# v1.net
KiCad netlist of a schematic drawn in EAGLE
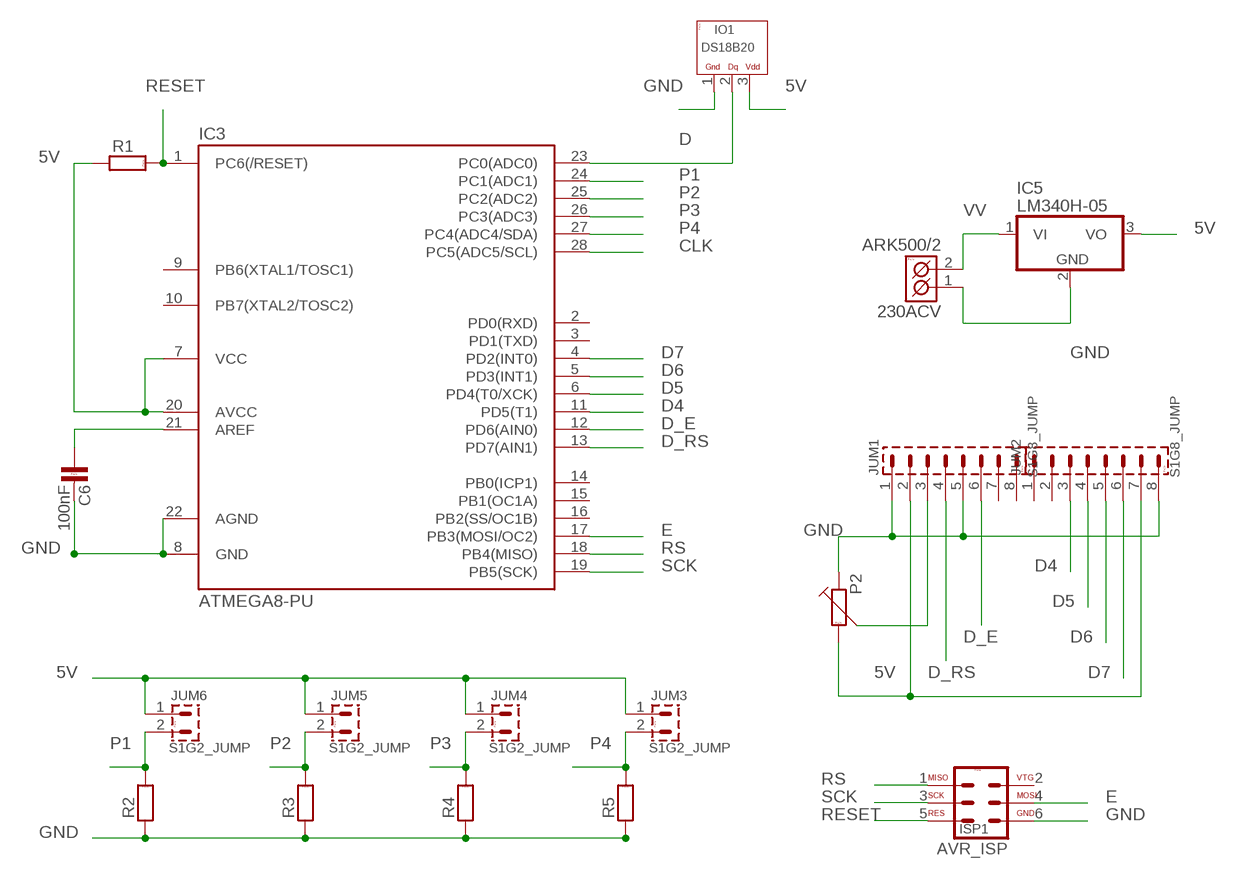
[diagram p0: schematic, sheet 1]

(export (version "E")
  (design (tool "Eeschema 10.0.6"))
  (components
    (comp (ref "230ACV")
      (value "ARK500/2")
      (footprint "eagle-import:ARK500_2")
      (libsource (lib "eagle-import") (part "ARK500/2"))
    )
    (comp (ref "C6")
      (value "100nF")
      (footprint "eagle-import:C-2,5")
      (libsource (lib "eagle-import") (part "C-KER_2,5"))
    )
    (comp (ref "IC3")
      (value "ATMEGA8-PU")
      (footprint "eagle-import:DIL28-3")
      (libsource (lib "eagle-import") (part "ATMEGA8-PU"))
    )
    (comp (ref "IC5")
      (value "LM340H-05")
      (footprint "eagle-import:TO220H")
      (libsource (lib "eagle-import") (part "LM340?-H05"))
    )
    (comp (ref "IO1")
      (value "DS18B20")
      (footprint "eagle-import:TO-92")
      (libsource (lib "eagle-import") (part "DS18B20"))
    )
    (comp (ref "ISP1")
      (value "AVR_ISP")
      (footprint "eagle-import:MLW06G")
      (libsource (lib "eagle-import") (part "AVR_ISP"))
    )
    (comp (ref "JUM1")
      (value "S1G8_JUMP")
      (footprint "eagle-import:S1G8_JUM")
      (libsource (lib "eagle-import") (part "S1G8_JUMP"))
    )
    (comp (ref "JUM2")
      (value "S1G8_JUMP")
      (footprint "eagle-import:S1G8_JUM")
      (libsource (lib "eagle-import") (part "S1G8_JUMP"))
    )
    (comp (ref "JUM3")
      (value "S1G2_JUMP")
      (footprint "eagle-import:S1G2_JUM")
      (libsource (lib "eagle-import") (part "S1G2_JUMP"))
    )
    (comp (ref "JUM4")
      (value "S1G2_JUMP")
      (footprint "eagle-import:S1G2_JUM")
      (libsource (lib "eagle-import") (part "S1G2_JUMP"))
    )
    (comp (ref "JUM5")
      (value "S1G2_JUMP")
      (footprint "eagle-import:S1G2_JUM")
      (libsource (lib "eagle-import") (part "S1G2_JUMP"))
    )
    (comp (ref "JUM6")
      (value "S1G2_JUMP")
      (footprint "eagle-import:S1G2_JUM")
      (libsource (lib "eagle-import") (part "S1G2_JUMP"))
    )
    (comp (ref "P2")
      (value "TRIMRPT6V")
      (footprint "eagle-import:PT6V")
      (libsource (lib "eagle-import") (part "TRIMRPT6V"))
    )
    (comp (ref "R1")
      (value "R_7,5")
      (footprint "eagle-import:R-7,5")
      (libsource (lib "eagle-import") (part "R_7,5"))
    )
    (comp (ref "R2")
      (value "R_7,5")
      (footprint "eagle-import:R-7,5")
      (libsource (lib "eagle-import") (part "R_7,5"))
    )
    (comp (ref "R3")
      (value "R_7,5")
      (footprint "eagle-import:R-7,5")
      (libsource (lib "eagle-import") (part "R_7,5"))
    )
    (comp (ref "R4")
      (value "R_7,5")
      (footprint "eagle-import:R-7,5")
      (libsource (lib "eagle-import") (part "R_7,5"))
    )
    (comp (ref "R5")
      (value "R_7,5")
      (footprint "eagle-import:R-7,5")
      (libsource (lib "eagle-import") (part "R_7,5"))
    )
  )
  (nets
    (net (code "1") (name "/5V") (class "Default")
      (node (ref "IC3") (pin "20") (pinfunction "AVCC_20") (pintype "passive"))
      (node (ref "IC3") (pin "7") (pinfunction "VCC_7") (pintype "power_in"))
      (node (ref "IC5") (pin "3") (pinfunction "VO_3") (pintype "passive"))
      (node (ref "IO1") (pin "3") (pinfunction "+VCC_3") (pintype "power_in"))
      (node (ref "JUM1") (pin "2") (pinfunction "2_2") (pintype "passive"))
      (node (ref "JUM2") (pin "7") (pinfunction "7_7") (pintype "passive"))
      (node (ref "JUM3") (pin "1") (pinfunction "1_1") (pintype "passive"))
      (node (ref "JUM4") (pin "1") (pinfunction "1_1") (pintype "passive"))
      (node (ref "JUM5") (pin "1") (pinfunction "1_1") (pintype "passive"))
      (node (ref "JUM6") (pin "1") (pinfunction "1_1") (pintype "passive"))
      (node (ref "P2") (pin "2") (pinfunction "2_2") (pintype "passive"))
      (node (ref "R1") (pin "1") (pinfunction "1_1") (pintype "passive"))
    )
    (net (code "2") (name "/CLK") (class "Default")
      (node (ref "IC3") (pin "28") (pinfunction "PC5(ADC5/SCL)_28") (pintype "bidirectional"))
    )
    (net (code "3") (name "/D") (class "Default")
      (node (ref "IC3") (pin "23") (pinfunction "PC0(ADC0)_23") (pintype "bidirectional"))
      (node (ref "IO1") (pin "2") (pinfunction "1WIRE_2") (pintype "bidirectional"))
    )
    (net (code "4") (name "/D4") (class "Default")
      (node (ref "IC3") (pin "11") (pinfunction "PD5(T1)_11") (pintype "bidirectional"))
      (node (ref "JUM2") (pin "3") (pinfunction "3_3") (pintype "passive"))
    )
    (net (code "5") (name "/D5") (class "Default")
      (node (ref "IC3") (pin "6") (pinfunction "PD4(T0/XCK)_6") (pintype "bidirectional"))
      (node (ref "JUM2") (pin "4") (pinfunction "4_4") (pintype "passive"))
    )
    (net (code "6") (name "/D6") (class "Default")
      (node (ref "IC3") (pin "5") (pinfunction "PD3(INT1)_5") (pintype "bidirectional"))
      (node (ref "JUM2") (pin "5") (pinfunction "5_5") (pintype "passive"))
    )
    (net (code "7") (name "/D7") (class "Default")
      (node (ref "IC3") (pin "4") (pinfunction "PD2(INT0)_4") (pintype "bidirectional"))
      (node (ref "JUM2") (pin "6") (pinfunction "6_6") (pintype "passive"))
    )
    (net (code "8") (name "/D_E") (class "Default")
      (node (ref "IC3") (pin "12") (pinfunction "PD6(AIN0)_12") (pintype "bidirectional"))
      (node (ref "JUM1") (pin "6") (pinfunction "6_6") (pintype "passive"))
    )
    (net (code "9") (name "/D_RS") (class "Default")
      (node (ref "IC3") (pin "13") (pinfunction "PD7(AIN1)_13") (pintype "bidirectional"))
      (node (ref "JUM1") (pin "4") (pinfunction "4_4") (pintype "passive"))
    )
    (net (code "10") (name "/E") (class "Default")
      (node (ref "IC3") (pin "17") (pinfunction "PB3(MOSI/OC2)_17") (pintype "bidirectional"))
      (node (ref "ISP1") (pin "4") (pinfunction "4_4") (pintype "passive"))
    )
    (net (code "11") (name "/GND") (class "Default")
      (node (ref "230ACV") (pin "1") (pinfunction "K1_1") (pintype "passive"))
      (node (ref "C6") (pin "2") (pinfunction "2_2") (pintype "passive"))
      (node (ref "IC3") (pin "22") (pinfunction "AGND_22") (pintype "power_in"))
      (node (ref "IC3") (pin "8") (pinfunction "GND_8") (pintype "power_in"))
      (node (ref "IC5") (pin "2") (pinfunction "GND_2") (pintype "passive"))
      (node (ref "IO1") (pin "1") (pinfunction "GND_1") (pintype "power_in"))
      (node (ref "ISP1") (pin "6") (pinfunction "6_6") (pintype "passive"))
      (node (ref "JUM1") (pin "1") (pinfunction "1_1") (pintype "passive"))
      (node (ref "JUM1") (pin "5") (pinfunction "5_5") (pintype "passive"))
      (node (ref "JUM2") (pin "8") (pinfunction "8_8") (pintype "passive"))
      (node (ref "P2") (pin "1") (pinfunction "1_1") (pintype "passive"))
      (node (ref "R2") (pin "1") (pinfunction "1_1") (pintype "passive"))
      (node (ref "R3") (pin "1") (pinfunction "1_1") (pintype "passive"))
      (node (ref "R4") (pin "1") (pinfunction "1_1") (pintype "passive"))
      (node (ref "R5") (pin "1") (pinfunction "1_1") (pintype "passive"))
    )
    (net (code "12") (name "/P1") (class "Default")
      (node (ref "IC3") (pin "24") (pinfunction "PC1(ADC1)_24") (pintype "bidirectional"))
      (node (ref "JUM6") (pin "2") (pinfunction "2_2") (pintype "passive"))
      (node (ref "R2") (pin "2") (pinfunction "2_2") (pintype "passive"))
    )
    (net (code "13") (name "/P2") (class "Default")
      (node (ref "IC3") (pin "25") (pinfunction "PC2(ADC2)_25") (pintype "bidirectional"))
      (node (ref "JUM5") (pin "2") (pinfunction "2_2") (pintype "passive"))
      (node (ref "R3") (pin "2") (pinfunction "2_2") (pintype "passive"))
    )
    (net (code "14") (name "/P3") (class "Default")
      (node (ref "IC3") (pin "26") (pinfunction "PC3(ADC3)_26") (pintype "bidirectional"))
      (node (ref "JUM4") (pin "2") (pinfunction "2_2") (pintype "passive"))
      (node (ref "R4") (pin "2") (pinfunction "2_2") (pintype "passive"))
    )
    (net (code "15") (name "/P4") (class "Default")
      (node (ref "IC3") (pin "27") (pinfunction "PC4(ADC4/SDA)_27") (pintype "bidirectional"))
      (node (ref "JUM3") (pin "2") (pinfunction "2_2") (pintype "passive"))
      (node (ref "R5") (pin "2") (pinfunction "2_2") (pintype "passive"))
    )
    (net (code "16") (name "/RESET") (class "Default")
      (node (ref "IC3") (pin "1") (pinfunction "PC6(/RESET)_1") (pintype "bidirectional"))
      (node (ref "ISP1") (pin "5") (pinfunction "5_5") (pintype "passive"))
      (node (ref "R1") (pin "2") (pinfunction "2_2") (pintype "passive"))
    )
    (net (code "17") (name "/RS") (class "Default")
      (node (ref "IC3") (pin "18") (pinfunction "PB4(MISO)_18") (pintype "bidirectional"))
      (node (ref "ISP1") (pin "1") (pinfunction "1_1") (pintype "passive"))
    )
    (net (code "18") (name "/SCK") (class "Default")
      (node (ref "IC3") (pin "19") (pinfunction "PB5(SCK)_19") (pintype "bidirectional"))
      (node (ref "ISP1") (pin "3") (pinfunction "3_3") (pintype "passive"))
    )
    (net (code "19") (name "/VV") (class "Default")
      (node (ref "230ACV") (pin "2") (pinfunction "K2_2") (pintype "passive"))
      (node (ref "IC5") (pin "1") (pinfunction "VI_1") (pintype "input"))
    )
    (net (code "20") (name "Net-(IC3-AREF)") (class "Default")
      (node (ref "C6") (pin "1") (pinfunction "1_1") (pintype "passive"))
      (node (ref "IC3") (pin "21") (pinfunction "AREF_21") (pintype "passive"))
    )
    (net (code "21") (name "Net-(JUM1-Pad3)") (class "Default")
      (node (ref "JUM1") (pin "3") (pinfunction "3_3") (pintype "passive"))
      (node (ref "P2") (pin "3") (pinfunction "3_3") (pintype "passive"))
    )
    (net (code "22") (name "unconnected-(IC3-PB0(ICP1)-Pad14)") (class "Default")
      (node (ref "IC3") (pin "14") (pinfunction "PB0(ICP1)_14") (pintype "bidirectional"))
    )
    (net (code "23") (name "unconnected-(IC3-PB1(OC1A)-Pad15)") (class "Default")
      (node (ref "IC3") (pin "15") (pinfunction "PB1(OC1A)_15") (pintype "bidirectional"))
    )
    (net (code "24") (name "unconnected-(IC3-PB2(SS{slash}OC1B)-Pad16)") (class "Default")
      (node (ref "IC3") (pin "16") (pinfunction "PB2(SS/OC1B)_16") (pintype "bidirectional"))
    )
    (net (code "25") (name "unconnected-(IC3-PB6(XTAL1{slash}TOSC1)-Pad9)") (class "Default")
      (node (ref "IC3") (pin "9") (pinfunction "PB6(XTAL1/TOSC1)_9") (pintype "bidirectional"))
    )
    (net (code "26") (name "unconnected-(IC3-PB7(XTAL2{slash}TOSC2)-Pad10)") (class "Default")
      (node (ref "IC3") (pin "10") (pinfunction "PB7(XTAL2/TOSC2)_10") (pintype "bidirectional"))
    )
    (net (code "27") (name "unconnected-(IC3-PD0(RXD)-Pad2)") (class "Default")
      (node (ref "IC3") (pin "2") (pinfunction "PD0(RXD)_2") (pintype "bidirectional"))
    )
    (net (code "28") (name "unconnected-(IC3-PD1(TXD)-Pad3)") (class "Default")
      (node (ref "IC3") (pin "3") (pinfunction "PD1(TXD)_3") (pintype "bidirectional"))
    )
    (net (code "29") (name "unconnected-(ISP1-Pad2)") (class "Default")
      (node (ref "ISP1") (pin "2") (pinfunction "2_2") (pintype "passive"))
    )
    (net (code "30") (name "unconnected-(JUM1-Pad7)") (class "Default")
      (node (ref "JUM1") (pin "7") (pinfunction "7_7") (pintype "passive"))
    )
    (net (code "31") (name "unconnected-(JUM1-Pad8)") (class "Default")
      (node (ref "JUM1") (pin "8") (pinfunction "8_8") (pintype "passive"))
    )
    (net (code "32") (name "unconnected-(JUM2-Pad1)") (class "Default")
      (node (ref "JUM2") (pin "1") (pinfunction "1_1") (pintype "passive"))
    )
    (net (code "33") (name "unconnected-(JUM2-Pad2)") (class "Default")
      (node (ref "JUM2") (pin "2") (pinfunction "2_2") (pintype "passive"))
    )
  )
)
